# modem2.net
KiCad netlist of a schematic drawn in EAGLE
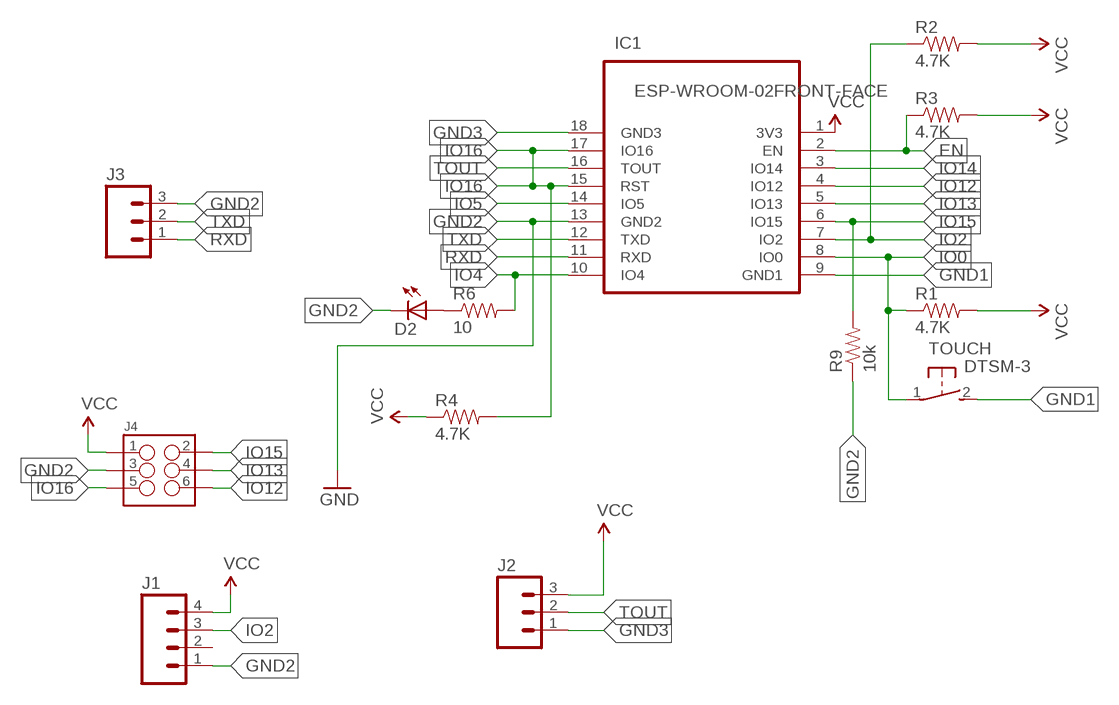
[diagram p0: schematic, sheet 1]

(export (version "E")
  (design (tool "Eeschema 10.0.6"))
  (components
    (comp (ref "D2")
      (value "LEDCHIPLED_0805")
      (footprint "eagle-import:CHIPLED_0805")
      (libsource (lib "eagle-import") (part "LEDCHIPLED_0805"))
    )
    (comp (ref "IC1")
      (value "ESP-WROOM-02FRONT-FACE")
      (footprint "eagle-import:FRONT-FACE")
      (libsource (lib "eagle-import") (part "ESP-WROOM-02FRONT-FACE"))
    )
    (comp (ref "J1")
      (value "M04NO_SILK_ALL_ROUND")
      (footprint "eagle-import:1X04_NO_SILK_ALL_ROUND")
      (libsource (lib "eagle-import") (part "M04NO_SILK_ALL_ROUND"))
    )
    (comp (ref "J2")
      (value "M03PTH")
      (footprint "eagle-import:1X03")
      (libsource (lib "eagle-import") (part "M03PTH"))
    )
    (comp (ref "J3")
      (value "M031X03_NO_SILK")
      (footprint "eagle-import:1X03_NO_SILK")
      (libsource (lib "eagle-import") (part "M031X03_NO_SILK"))
    )
    (comp (ref "J4")
      (value "M03X2SHROUD")
      (footprint "eagle-import:2X3-SHROUDED")
      (libsource (lib "eagle-import") (part "M03X2SHROUD"))
    )
    (comp (ref "R1")
      (value "4.7K")
      (footprint "eagle-import:0805")
      (libsource (lib "eagle-import") (part "RESISTOR0805-RES"))
    )
    (comp (ref "R2")
      (value "4.7K")
      (footprint "eagle-import:0805")
      (libsource (lib "eagle-import") (part "RESISTOR0805-RES"))
    )
    (comp (ref "R3")
      (value "4.7K")
      (footprint "eagle-import:0805")
      (libsource (lib "eagle-import") (part "RESISTOR0805-RES"))
    )
    (comp (ref "R4")
      (value "4.7K")
      (footprint "eagle-import:0805")
      (libsource (lib "eagle-import") (part "RESISTOR0805-RES"))
    )
    (comp (ref "R6")
      (value "10")
      (footprint "eagle-import:0805")
      (libsource (lib "eagle-import") (part "RESISTOR0805-RES"))
    )
    (comp (ref "R9")
      (value "10k")
      (footprint "eagle-import:0805")
      (libsource (lib "eagle-import") (part "RESISTOR0805-RES"))
    )
    (comp (ref "TOUCH")
      (value "DTSM-3")
      (footprint "eagle-import:DTSM-3")
      (libsource (lib "eagle-import") (part "DTSM-3"))
    )
  )
  (nets
    (net (code "1") (name "EN") (class "Default")
      (node (ref "IC1") (pin "2") (pinfunction "EN_2") (pintype "bidirectional"))
      (node (ref "R3") (pin "1") (pinfunction "1_1") (pintype "passive"))
    )
    (net (code "2") (name "GND1") (class "Default")
      (node (ref "IC1") (pin "9") (pinfunction "GND1_9") (pintype "power_in"))
      (node (ref "TOUCH") (pin "2") (pinfunction "2_2") (pintype "passive"))
    )
    (net (code "3") (name "GND2") (class "Default")
      (node (ref "D2") (pin "C") (pinfunction "C_C") (pintype "passive"))
      (node (ref "IC1") (pin "13") (pinfunction "GND2_13") (pintype "power_in"))
      (node (ref "J1") (pin "1") (pinfunction "1_1") (pintype "passive"))
      (node (ref "J3") (pin "3") (pinfunction "3_3") (pintype "passive"))
      (node (ref "J4") (pin "3") (pinfunction "3_3") (pintype "bidirectional"))
      (node (ref "R9") (pin "1") (pinfunction "1_1") (pintype "passive"))
    )
    (net (code "4") (name "GND3") (class "Default")
      (node (ref "IC1") (pin "18") (pinfunction "GND3_18") (pintype "power_in"))
      (node (ref "J2") (pin "1") (pinfunction "1_1") (pintype "passive"))
    )
    (net (code "5") (name "IO0") (class "Default")
      (node (ref "IC1") (pin "8") (pinfunction "IO0_8") (pintype "bidirectional"))
      (node (ref "R1") (pin "1") (pinfunction "1_1") (pintype "passive"))
      (node (ref "TOUCH") (pin "1") (pinfunction "1_1") (pintype "passive"))
    )
    (net (code "6") (name "IO2") (class "Default")
      (node (ref "IC1") (pin "7") (pinfunction "IO2_7") (pintype "bidirectional"))
      (node (ref "J1") (pin "3") (pinfunction "3_3") (pintype "passive"))
      (node (ref "R2") (pin "1") (pinfunction "1_1") (pintype "passive"))
    )
    (net (code "7") (name "IO4") (class "Default")
      (node (ref "IC1") (pin "10") (pinfunction "IO4_10") (pintype "bidirectional"))
      (node (ref "R6") (pin "2") (pinfunction "2_2") (pintype "passive"))
    )
    (net (code "8") (name "IO5") (class "Default")
      (node (ref "IC1") (pin "14") (pinfunction "IO5_14") (pintype "open_collector"))
    )
    (net (code "9") (name "IO12") (class "Default")
      (node (ref "IC1") (pin "4") (pinfunction "IO12_4") (pintype "bidirectional"))
      (node (ref "J4") (pin "6") (pinfunction "6_6") (pintype "bidirectional"))
    )
    (net (code "10") (name "IO13") (class "Default")
      (node (ref "IC1") (pin "5") (pinfunction "IO13_5") (pintype "bidirectional"))
      (node (ref "J4") (pin "4") (pinfunction "4_4") (pintype "bidirectional"))
    )
    (net (code "11") (name "IO14") (class "Default")
      (node (ref "IC1") (pin "3") (pinfunction "IO14_3") (pintype "bidirectional"))
    )
    (net (code "12") (name "IO15") (class "Default")
      (node (ref "IC1") (pin "6") (pinfunction "IO15_6") (pintype "bidirectional"))
      (node (ref "J4") (pin "2") (pinfunction "2_2") (pintype "bidirectional"))
      (node (ref "R9") (pin "2") (pinfunction "2_2") (pintype "passive"))
    )
    (net (code "13") (name "IO16") (class "Default")
      (node (ref "IC1") (pin "15") (pinfunction "RST_15") (pintype "bidirectional"))
      (node (ref "IC1") (pin "17") (pinfunction "IO16_17") (pintype "bidirectional"))
      (node (ref "J4") (pin "5") (pinfunction "5_5") (pintype "bidirectional"))
      (node (ref "R4") (pin "2") (pinfunction "2_2") (pintype "passive"))
    )
    (net (code "14") (name "Net-(D2-PadA)") (class "Default")
      (node (ref "D2") (pin "A") (pinfunction "A_A") (pintype "passive"))
      (node (ref "R6") (pin "1") (pinfunction "1_1") (pintype "passive"))
    )
    (net (code "15") (name "RXD") (class "Default")
      (node (ref "IC1") (pin "11") (pinfunction "RXD_11") (pintype "bidirectional"))
      (node (ref "J3") (pin "1") (pinfunction "1_1") (pintype "passive"))
    )
    (net (code "16") (name "TOUT") (class "Default")
      (node (ref "IC1") (pin "16") (pinfunction "TOUT_16") (pintype "bidirectional"))
      (node (ref "J2") (pin "2") (pinfunction "2_2") (pintype "passive"))
    )
    (net (code "17") (name "TXD") (class "Default")
      (node (ref "IC1") (pin "12") (pinfunction "TXD_12") (pintype "bidirectional"))
      (node (ref "J3") (pin "2") (pinfunction "2_2") (pintype "passive"))
    )
    (net (code "18") (name "VCC") (class "Default")
      (node (ref "IC1") (pin "1") (pinfunction "3V3_1") (pintype "power_in"))
      (node (ref "J1") (pin "4") (pinfunction "4_4") (pintype "passive"))
      (node (ref "J2") (pin "3") (pinfunction "3_3") (pintype "passive"))
      (node (ref "J4") (pin "1") (pinfunction "1_1") (pintype "bidirectional"))
      (node (ref "R1") (pin "2") (pinfunction "2_2") (pintype "passive"))
      (node (ref "R2") (pin "2") (pinfunction "2_2") (pintype "passive"))
      (node (ref "R3") (pin "2") (pinfunction "2_2") (pintype "passive"))
      (node (ref "R4") (pin "1") (pinfunction "1_1") (pintype "passive"))
    )
    (net (code "19") (name "unconnected-(J1-Pad2)") (class "Default")
      (node (ref "J1") (pin "2") (pinfunction "2_2") (pintype "passive"))
    )
  )
)
